# 1tda2030b.net
KiCad netlist of a schematic drawn in EAGLE
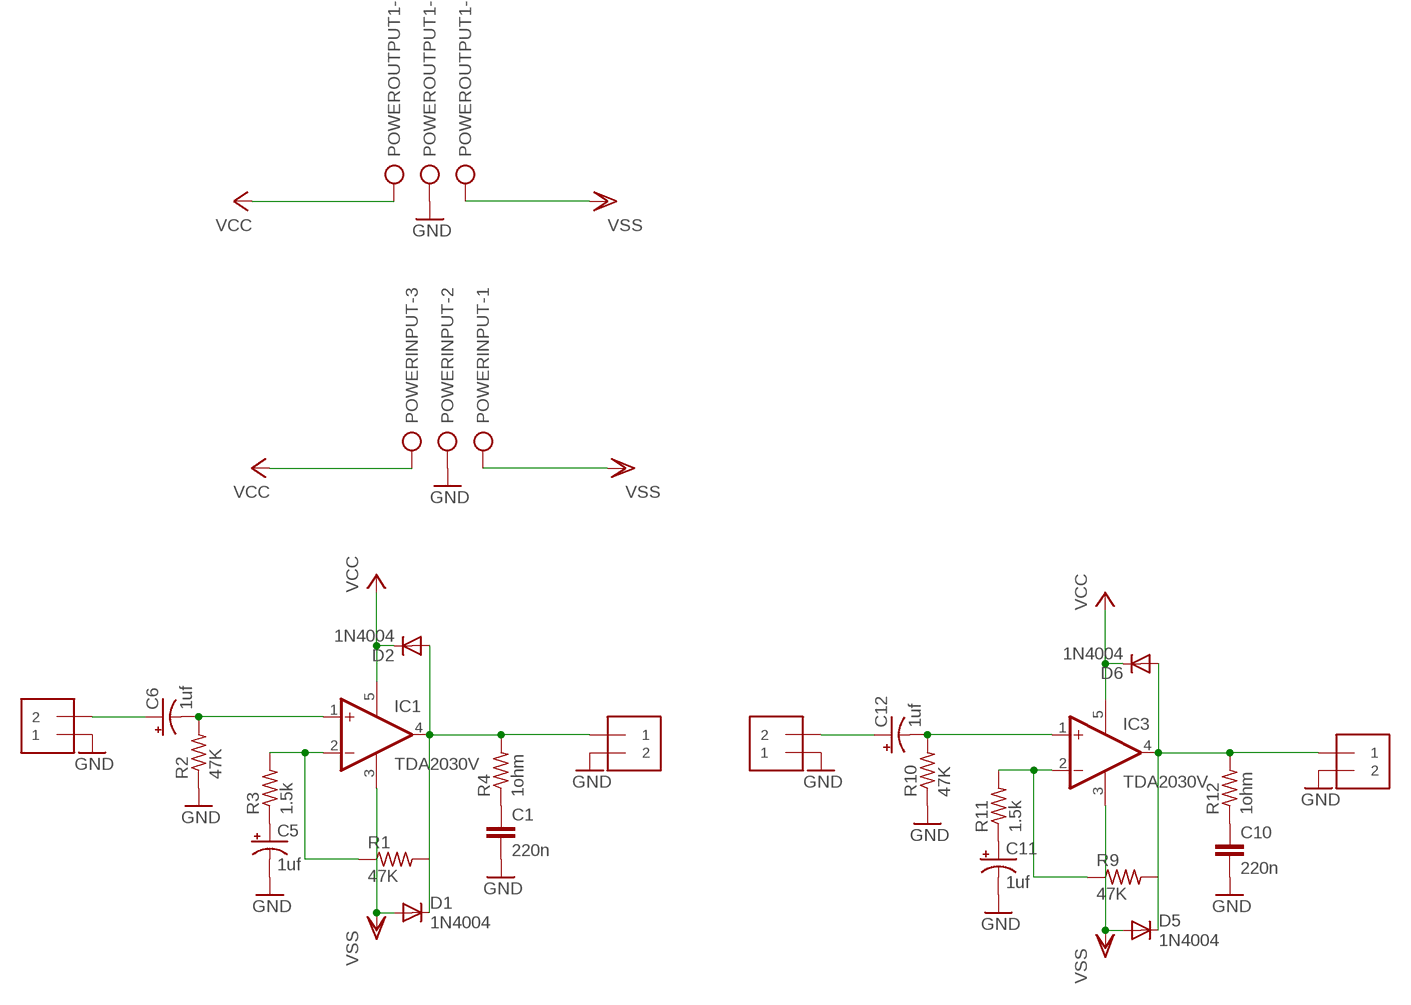
[diagram p0: schematic, sheet 1]

(export (version "E")
  (design (tool "Eeschema 10.0.6"))
  (components
    (comp (ref "1STI/P")
      (value "1X2-3.5MM")
      (footprint "eagle-import:1X2-3.5MM")
      (libsource (lib "eagle-import") (part "1X2-3.5MM"))
    )
    (comp (ref "1STO/P")
      (value "1X2-3.5MM")
      (footprint "eagle-import:1X2-3.5MM")
      (libsource (lib "eagle-import") (part "1X2-3.5MM"))
    )
    (comp (ref "2NDI/P")
      (value "1X2-3.5MM")
      (footprint "eagle-import:1X2-3.5MM")
      (libsource (lib "eagle-import") (part "1X2-3.5MM"))
    )
    (comp (ref "2NDO/P")
      (value "1X2-3.5MM")
      (footprint "eagle-import:1X2-3.5MM")
      (libsource (lib "eagle-import") (part "1X2-3.5MM"))
    )
    (comp (ref "C1")
      (value "220n")
      (footprint "eagle-import:CAP-PTH-SMALL-KIT")
      (libsource (lib "eagle-import") (part "0.1UF-KIT-EZ-50V-20%"))
    )
    (comp (ref "C5")
      (value "1uf")
      (footprint "eagle-import:E5-8,5")
      (libsource (lib "eagle-import") (part "CPOL-USE5-8.5"))
    )
    (comp (ref "C6")
      (value "1uf")
      (footprint "eagle-import:E5-8,5")
      (libsource (lib "eagle-import") (part "CPOL-USE5-8.5"))
    )
    (comp (ref "C10")
      (value "220n")
      (footprint "eagle-import:CAP-PTH-SMALL-KIT")
      (libsource (lib "eagle-import") (part "0.1UF-KIT-EZ-50V-20%"))
    )
    (comp (ref "C11")
      (value "1uf")
      (footprint "eagle-import:E5-8,5")
      (libsource (lib "eagle-import") (part "CPOL-USE5-8.5"))
    )
    (comp (ref "C12")
      (value "1uf")
      (footprint "eagle-import:E5-8,5")
      (libsource (lib "eagle-import") (part "CPOL-USE5-8.5"))
    )
    (comp (ref "D1")
      (value "1N4004")
      (footprint "eagle-import:DO41-10")
      (libsource (lib "eagle-import") (part "1N4004"))
    )
    (comp (ref "D2")
      (value "1N4004")
      (footprint "eagle-import:DO41-10")
      (libsource (lib "eagle-import") (part "1N4004"))
    )
    (comp (ref "D5")
      (value "1N4004")
      (footprint "eagle-import:DO41-10")
      (libsource (lib "eagle-import") (part "1N4004"))
    )
    (comp (ref "D6")
      (value "1N4004")
      (footprint "eagle-import:DO41-10")
      (libsource (lib "eagle-import") (part "1N4004"))
    )
    (comp (ref "IC1")
      (value "TDA2030V")
      (footprint "eagle-import:CB360")
      (libsource (lib "eagle-import") (part "TDA2030V"))
    )
    (comp (ref "IC3")
      (value "TDA2030V")
      (footprint "eagle-import:CB360")
      (libsource (lib "eagle-import") (part "TDA2030V"))
    )
    (comp (ref "POWERINPUT")
      (value "AK300/3")
      (footprint "eagle-import:AK300_3")
      (libsource (lib "eagle-import") (part "AK300/3"))
    )
    (comp (ref "POWEROUTPUT1")
      (value "AK300/3")
      (footprint "eagle-import:AK300_3")
      (libsource (lib "eagle-import") (part "AK300/3"))
    )
    (comp (ref "R1")
      (value "47K")
      (footprint "eagle-import:0805-THM")
      (libsource (lib "eagle-import") (part "FLIPFLOP-RES"))
    )
    (comp (ref "R2")
      (value "47K")
      (footprint "eagle-import:0805-THM")
      (libsource (lib "eagle-import") (part "FLIPFLOP-RES"))
    )
    (comp (ref "R3")
      (value "1.5k")
      (footprint "eagle-import:0805-THM")
      (libsource (lib "eagle-import") (part "FLIPFLOP-RES"))
    )
    (comp (ref "R4")
      (value "1ohm")
      (footprint "eagle-import:0805-THM")
      (libsource (lib "eagle-import") (part "FLIPFLOP-RES"))
    )
    (comp (ref "R9")
      (value "47K")
      (footprint "eagle-import:0805-THM")
      (libsource (lib "eagle-import") (part "FLIPFLOP-RES"))
    )
    (comp (ref "R10")
      (value "47K")
      (footprint "eagle-import:0805-THM")
      (libsource (lib "eagle-import") (part "FLIPFLOP-RES"))
    )
    (comp (ref "R11")
      (value "1.5k")
      (footprint "eagle-import:0805-THM")
      (libsource (lib "eagle-import") (part "FLIPFLOP-RES"))
    )
    (comp (ref "R12")
      (value "1ohm")
      (footprint "eagle-import:0805-THM")
      (libsource (lib "eagle-import") (part "FLIPFLOP-RES"))
    )
  )
  (nets
    (net (code "1") (name "GND") (class "Default")
      (node (ref "1STI/P") (pin "1") (pinfunction "1_1") (pintype "passive"))
      (node (ref "1STO/P") (pin "2") (pinfunction "2_2") (pintype "passive"))
      (node (ref "2NDI/P") (pin "1") (pinfunction "1_1") (pintype "passive"))
      (node (ref "2NDO/P") (pin "2") (pinfunction "2_2") (pintype "passive"))
      (node (ref "C1") (pin "2") (pinfunction "2_2") (pintype "passive"))
      (node (ref "C10") (pin "2") (pinfunction "2_2") (pintype "passive"))
      (node (ref "C11") (pin "-") (pinfunction "-_-") (pintype "passive"))
      (node (ref "C5") (pin "-") (pinfunction "-_-") (pintype "passive"))
      (node (ref "POWERINPUT") (pin "2") (pinfunction "KL_2") (pintype "passive"))
      (node (ref "POWEROUTPUT1") (pin "2") (pinfunction "KL_2") (pintype "passive"))
      (node (ref "R10") (pin "1") (pinfunction "1_1") (pintype "passive"))
      (node (ref "R2") (pin "1") (pinfunction "1_1") (pintype "passive"))
    )
    (net (code "2") (name "Net-(1STI/P-Pad2)") (class "Default")
      (node (ref "1STI/P") (pin "2") (pinfunction "2_2") (pintype "passive"))
      (node (ref "C6") (pin "+") (pinfunction "+_+") (pintype "passive"))
    )
    (net (code "3") (name "Net-(2NDI/P-Pad2)") (class "Default")
      (node (ref "2NDI/P") (pin "2") (pinfunction "2_2") (pintype "passive"))
      (node (ref "C12") (pin "+") (pinfunction "+_+") (pintype "passive"))
    )
    (net (code "4") (name "Net-(C1-Pad1)") (class "Default")
      (node (ref "C1") (pin "1") (pinfunction "1_1") (pintype "passive"))
      (node (ref "R4") (pin "1") (pinfunction "1_1") (pintype "passive"))
    )
    (net (code "5") (name "Net-(C5-Pad+)") (class "Default")
      (node (ref "C5") (pin "+") (pinfunction "+_+") (pintype "passive"))
      (node (ref "R3") (pin "1") (pinfunction "1_1") (pintype "passive"))
    )
    (net (code "6") (name "Net-(C10-Pad1)") (class "Default")
      (node (ref "C10") (pin "1") (pinfunction "1_1") (pintype "passive"))
      (node (ref "R12") (pin "1") (pinfunction "1_1") (pintype "passive"))
    )
    (net (code "7") (name "Net-(C11-Pad+)") (class "Default")
      (node (ref "C11") (pin "+") (pinfunction "+_+") (pintype "passive"))
      (node (ref "R11") (pin "1") (pinfunction "1_1") (pintype "passive"))
    )
    (net (code "8") (name "Net-(IC1-+IN)") (class "Default")
      (node (ref "C6") (pin "-") (pinfunction "-_-") (pintype "passive"))
      (node (ref "IC1") (pin "1") (pinfunction "+IN_1") (pintype "input"))
      (node (ref "R2") (pin "2") (pinfunction "2_2") (pintype "passive"))
    )
    (net (code "9") (name "Net-(IC1--IN)") (class "Default")
      (node (ref "IC1") (pin "2") (pinfunction "-IN_2") (pintype "input"))
      (node (ref "R1") (pin "1") (pinfunction "1_1") (pintype "passive"))
      (node (ref "R3") (pin "2") (pinfunction "2_2") (pintype "passive"))
    )
    (net (code "10") (name "Net-(IC1-OUT)") (class "Default")
      (node (ref "1STO/P") (pin "1") (pinfunction "1_1") (pintype "passive"))
      (node (ref "D1") (pin "C") (pinfunction "C_C") (pintype "passive"))
      (node (ref "D2") (pin "A") (pinfunction "A_A") (pintype "passive"))
      (node (ref "IC1") (pin "4") (pinfunction "OUT_4") (pintype "output"))
      (node (ref "R1") (pin "2") (pinfunction "2_2") (pintype "passive"))
      (node (ref "R4") (pin "2") (pinfunction "2_2") (pintype "passive"))
    )
    (net (code "11") (name "Net-(IC3-+IN)") (class "Default")
      (node (ref "C12") (pin "-") (pinfunction "-_-") (pintype "passive"))
      (node (ref "IC3") (pin "1") (pinfunction "+IN_1") (pintype "input"))
      (node (ref "R10") (pin "2") (pinfunction "2_2") (pintype "passive"))
    )
    (net (code "12") (name "Net-(IC3--IN)") (class "Default")
      (node (ref "IC3") (pin "2") (pinfunction "-IN_2") (pintype "input"))
      (node (ref "R11") (pin "2") (pinfunction "2_2") (pintype "passive"))
      (node (ref "R9") (pin "1") (pinfunction "1_1") (pintype "passive"))
    )
    (net (code "13") (name "Net-(IC3-OUT)") (class "Default")
      (node (ref "2NDO/P") (pin "1") (pinfunction "1_1") (pintype "passive"))
      (node (ref "D5") (pin "C") (pinfunction "C_C") (pintype "passive"))
      (node (ref "D6") (pin "A") (pinfunction "A_A") (pintype "passive"))
      (node (ref "IC3") (pin "4") (pinfunction "OUT_4") (pintype "output"))
      (node (ref "R12") (pin "2") (pinfunction "2_2") (pintype "passive"))
      (node (ref "R9") (pin "2") (pinfunction "2_2") (pintype "passive"))
    )
    (net (code "14") (name "VCC") (class "Default")
      (node (ref "D2") (pin "C") (pinfunction "C_C") (pintype "passive"))
      (node (ref "D6") (pin "C") (pinfunction "C_C") (pintype "passive"))
      (node (ref "IC1") (pin "5") (pinfunction "V+_5") (pintype "power_in"))
      (node (ref "IC3") (pin "5") (pinfunction "V+_5") (pintype "power_in"))
      (node (ref "POWERINPUT") (pin "3") (pinfunction "KL_3") (pintype "passive"))
      (node (ref "POWEROUTPUT1") (pin "3") (pinfunction "KL_3") (pintype "passive"))
    )
    (net (code "15") (name "VSS") (class "Default")
      (node (ref "D1") (pin "A") (pinfunction "A_A") (pintype "passive"))
      (node (ref "D5") (pin "A") (pinfunction "A_A") (pintype "passive"))
      (node (ref "IC1") (pin "3") (pinfunction "GND_3") (pintype "power_in"))
      (node (ref "IC3") (pin "3") (pinfunction "GND_3") (pintype "power_in"))
      (node (ref "POWERINPUT") (pin "1") (pinfunction "KL_1") (pintype "passive"))
      (node (ref "POWEROUTPUT1") (pin "1") (pinfunction "KL_1") (pintype "passive"))
    )
  )
)
